# mimosa_host_fsr_sch.net
KiCad netlist of a schematic drawn in Altium Designer
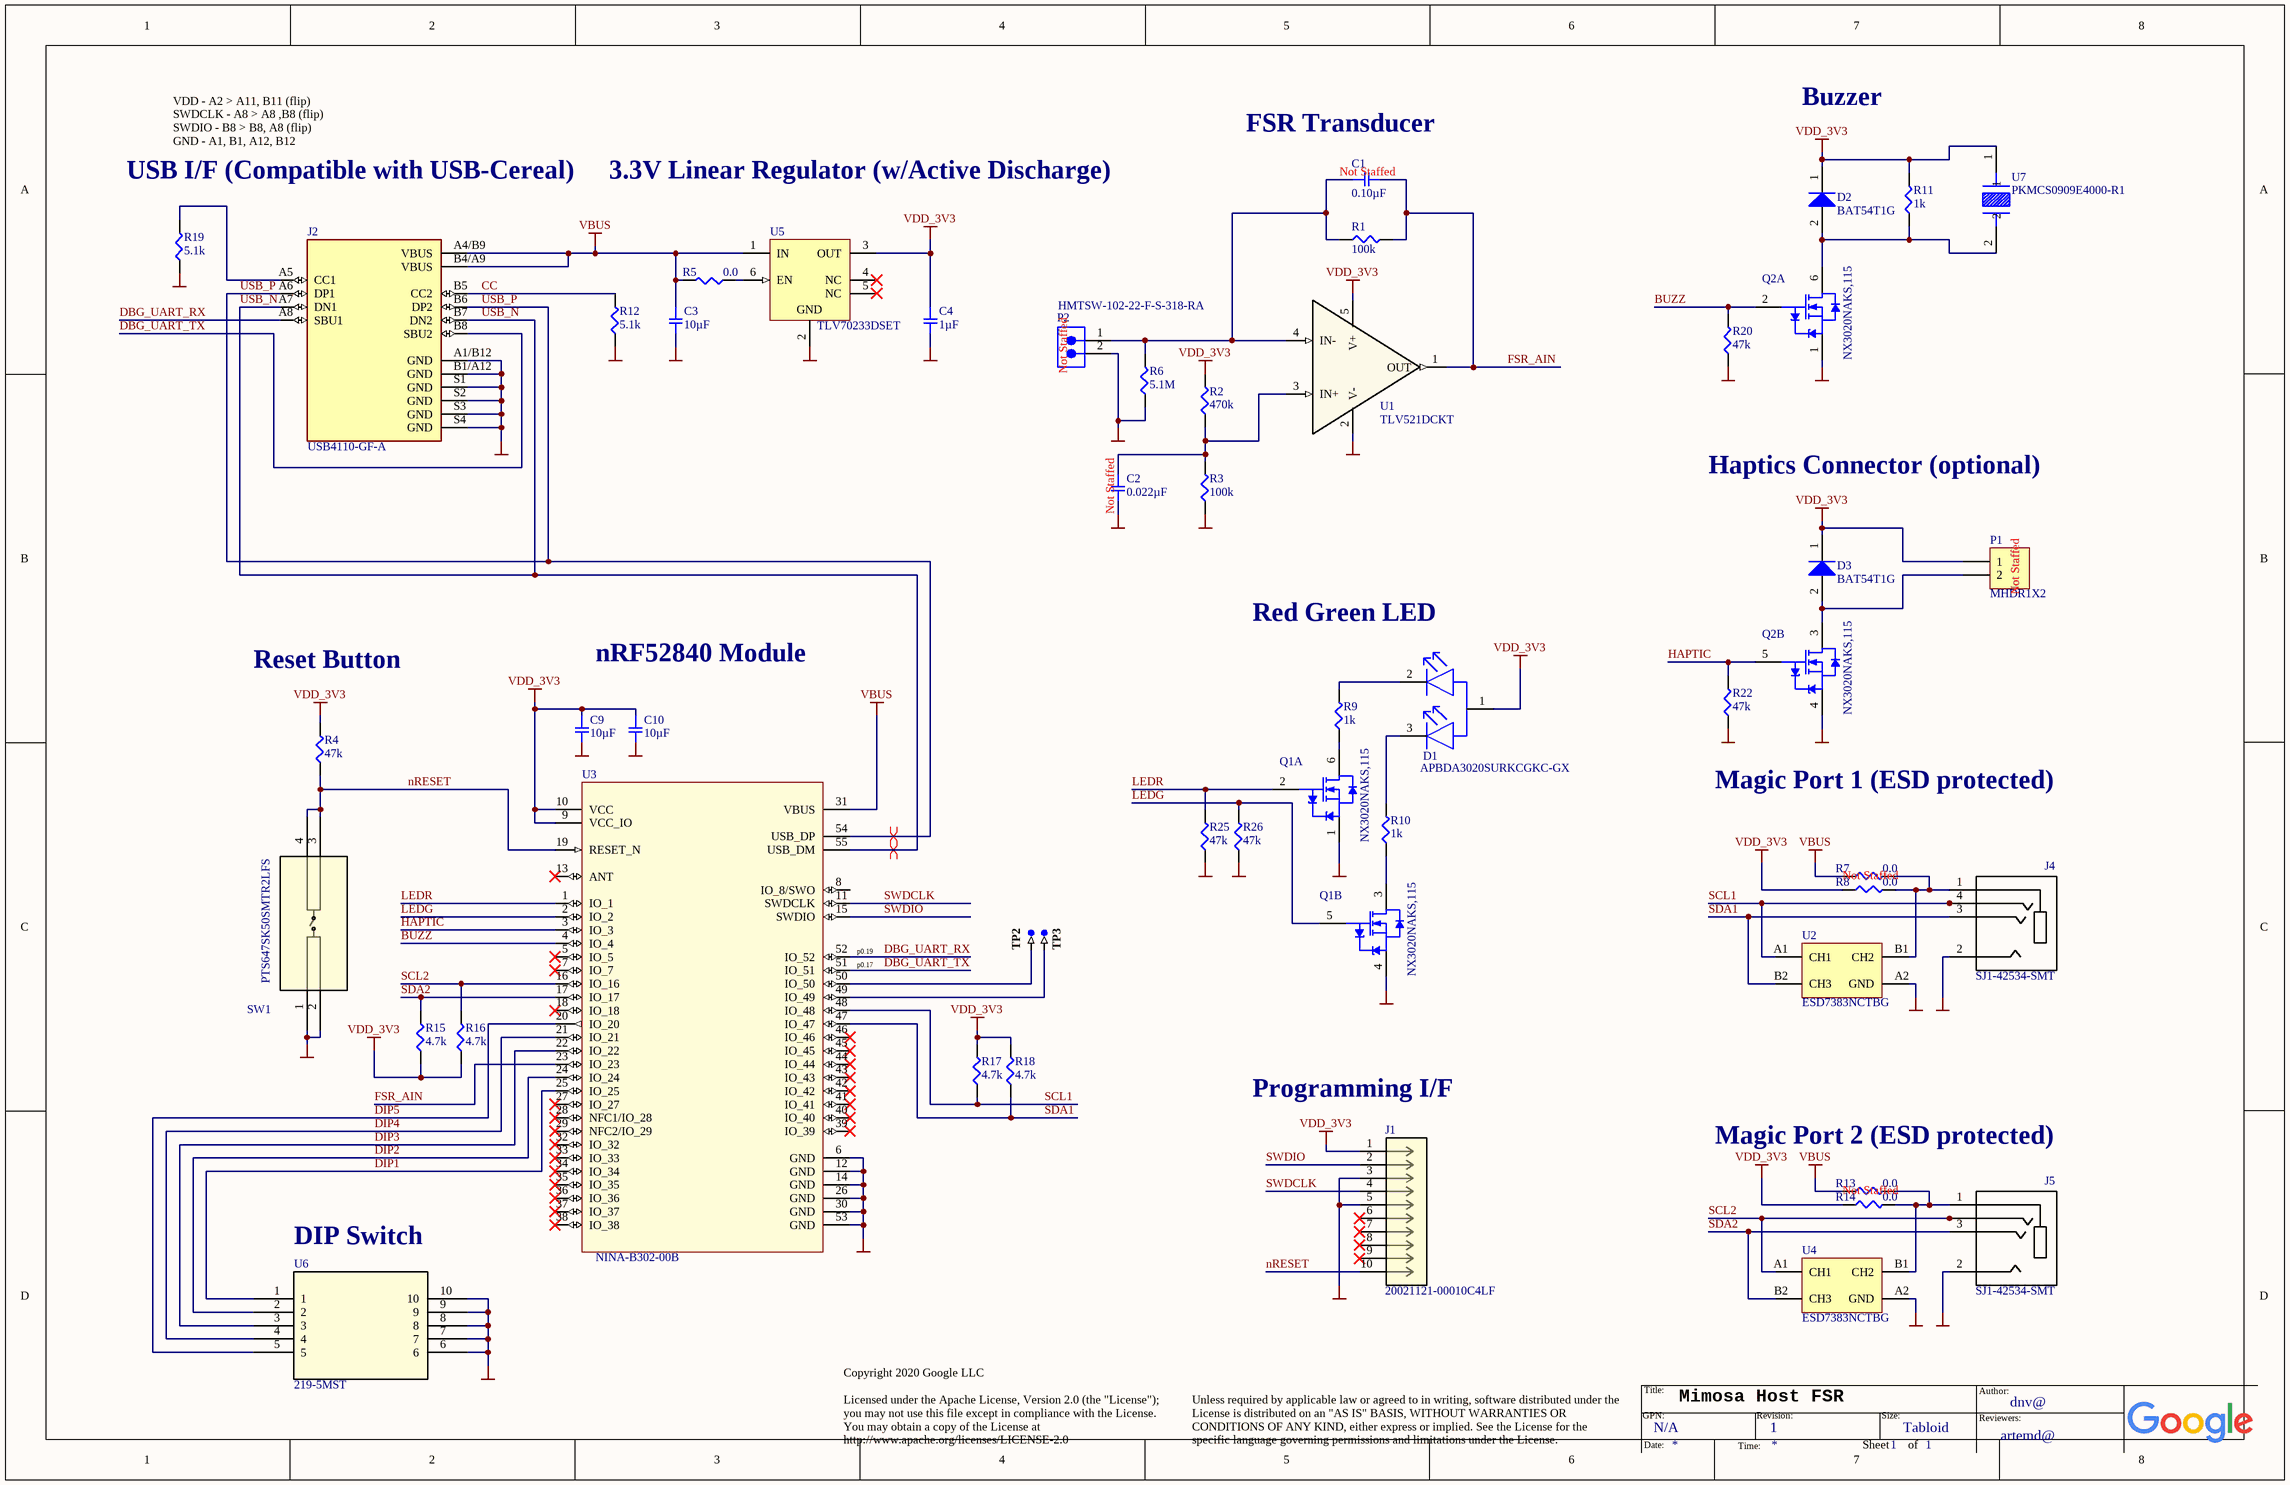
[diagram p0: mimosa_host_fsr_sch.SchDoc]

(export (version "E")
  (design (tool "Eeschema 10.0.6"))
  (components
    (comp (ref "C1")
      (value "0.10µF")
      (footprint "SMD-0201C")
      (description "CAP CER 0.1UF 10V X6S 0201")
      (fields
        (field (name "DIGI-KEY PART NUMBER") "490-12232-1-ND")
        (field (name "PART NUMBER") "GRT033C81A104KE01D")
      )
      (libsource (lib "cap_murata_0201") (part "GRT033C81A104KE01D"))
    )
    (comp (ref "C2")
      (value "0.022µF")
      (footprint "SMD-0201C")
      (description "CAP CER 0.022UF 6.3V X6S 0201")
      (fields
        (field (name "DIGI-KEY PART NUMBER") "490-8154-1-ND")
        (field (name "PART NUMBER") "GRM033C80J223KE01D")
      )
      (libsource (lib "cap_murata_0201") (part "GRM033C80J223KE01D"))
    )
    (comp (ref "C3")
      (value "10µF")
      (footprint "SMD-0402C")
      (description "CAP CER 10UF 6.3V X5R 0402")
      (fields
        (field (name "DIGI-KEY PART NUMBER") "490-13211-1-ND")
        (field (name "MPN") "GRJ155R60J106ME11D")
      )
      (libsource (lib "cap_murata_0402") (part "GRJ155R60J106ME11D"))
    )
    (comp (ref "C4")
      (value "1µF")
      (footprint "SMD-0201C")
      (description "CAP CER 1UF 6.3V X5R 0201")
      (fields
        (field (name "DIGI-KEY PART NUMBER") "490-7229-1-ND")
        (field (name "PART NUMBER") "GRM033R60J105MEA2D")
      )
      (libsource (lib "cap_murata_0201") (part "GRM033R60J105MEA2D"))
    )
    (comp (ref "C9")
      (value "10µF")
      (footprint "SMD-0402C")
      (description "CAP CER 10UF 6.3V X5R 0402")
      (fields
        (field (name "DIGI-KEY PART NUMBER") "490-13211-1-ND")
        (field (name "PART NUMBER") "GRJ155R60J106ME11D")
      )
      (libsource (lib "cap_murata_0402") (part "GRJ155R60J106ME11D"))
    )
    (comp (ref "C10")
      (value "10µF")
      (footprint "SMD-0402C")
      (description "CAP CER 10UF 6.3V X5R 0402")
      (fields
        (field (name "DIGI-KEY PART NUMBER") "490-13211-1-ND")
        (field (name "PART NUMBER") "GRJ155R60J106ME11D")
      )
      (libsource (lib "cap_murata_0402") (part "GRJ155R60J106ME11D"))
    )
    (comp (ref "D1")
      (value "APBDA3020SURKCGKC-GX")
      (footprint "Diode_Kingbright_APBDA3020SURKCGKC-GX_eec_MFG:Kingbright_0_MFG")
      (libsource (lib "Diode_Kingbright_APBDA3020SURKCGKC-GX_eec") (part "APBDA3020SURKCGKC-GX"))
    )
    (comp (ref "D2")
      (value "BAT54T1G")
      (footprint "ONSC-SOD-123-2-425-04_V")
      (description "Schottky Barrier Diode, 2-Pin SOD-123, Pb-Free, Tape and Reel")
      (fields (field (name "MANUFACTURER") "On Semiconductor"))
      (libsource (lib "diode_schottky_ON_Semi") (part "BAT54T1G"))
    )
    (comp (ref "D3")
      (value "BAT54T1G")
      (footprint "ONSC-SOD-123-2-425-04_V")
      (description "Schottky Barrier Diode, 2-Pin SOD-123, Pb-Free, Tape and Reel")
      (fields (field (name "MANUFACTURER") "On Semiconductor"))
      (libsource (lib "diode_schottky_ON_Semi") (part "BAT54T1G"))
    )
    (comp (ref "J1")
      (value "20021121-00010C4LF")
      (footprint "2020-07-28_02-37-58:CONN_00010C4LF_A")
      (description "No Description Available")
      (fields (field (name "COPYRIGHT") "Copyright (C) 2018 Accelerated Designs. All rights reserved"))
      (libsource (lib "2020-07-28_02-37-58") (part "20021121-00010C4"))
    )
    (comp (ref "J2")
      (value "USB4110-GF-A")
      (footprint "GCT_USB4110-GF-A")
      (fields (field (name "MF") "GCT") (field (name "DIGI-KEY_PART_NUMBER") "2073-USB4110-GF-A-1-ND"))
      (libsource (lib "USB4110-GF-A") (part "USB4110-GF-A"))
    )
    (comp (ref "J4")
      (value "SJ1-42534-SMT")
      (footprint "SJ1-42534-SMT:*CUI_SJ1-42534-SMT_SJ1-42534-SMT(Primary)")
      (description "2.5 mm, 4 Conductors, Right Angle, Surface Mount _SMT_, Audio Jack Connector")
      (fields
        (field (name "DIGI-KEY_PART_NUMBER") "CP1-42534SJCT-ND")
        (field (name "MANUFACTURER") "CUI Devices")
      )
      (libsource (lib "SJ1-42534-SMT") (part "SJ1-42534-SMT"))
    )
    (comp (ref "J5")
      (value "SJ1-42534-SMT")
      (footprint "SJ1-42534-SMT:*CUI_SJ1-42534-SMT_SJ1-42534-SMT(Primary)")
      (description "2.5 mm, 4 Conductors, Right Angle, Surface Mount _SMT_, Audio Jack Connector")
      (fields
        (field (name "DIGI-KEY_PART_NUMBER") "CP1-42534SJCT-ND")
        (field (name "MANUFACTURER") "CUI Devices")
      )
      (libsource (lib "SJ1-42534-SMT") (part "SJ1-42534-SMT"))
    )
    (comp (ref "P1")
      (value "MHDR1X2")
      (footprint "MHDR1X2")
      (description "Header, 2-Pin")
      (fields (field (name "PUBLISHER") "Altium Limited"))
      (libsource (lib "Miscellaneous Connectors") (part "MHDR1X2"))
    )
    (comp (ref "P2")
      (value "HMTSW-102-22-F-S-318-RA")
      (footprint "SMTC-HMTSW-102-22-X-S-318-RA")
      (fields (field (name "MANUFACTURER") "Samtec"))
      (libsource (lib "connector_samtec_2_54_mm") (part "HMTSW-102-22-F-S-318-RA"))
    )
    (comp (ref "Q1")
      (value "NX3020NAKS,115")
      (footprint "NXP-SOT363_N")
      (description "Dual N-Channel Trench MOSFET, 30 V, 0.18 A, -55 to 150 degC, 6-Pin SOT363, Tape and Reel")
      (fields (field (name "MANUFACTURER") "NXP Semiconductors"))
      (libsource (lib "transistor_NXP_standard_MOSFETs") (part "NX3020NAKS,115"))
    )
    (comp (ref "Q2")
      (value "NX3020NAKS,115")
      (footprint "NXP-SOT363_N")
      (description "Dual N-Channel Trench MOSFET, 30 V, 0.18 A, -55 to 150 degC, 6-Pin SOT363, Tape and Reel")
      (fields (field (name "MANUFACTURER") "NXP Semiconductors"))
      (libsource (lib "transistor_NXP_standard_MOSFETs") (part "NX3020NAKS,115"))
    )
    (comp (ref "R1")
      (value "100k")
      (footprint "SMD-0201-RES")
      (description "RES SMD 100K OHM 1% 1/20W 0201")
      (fields
        (field (name "PART NUMBER") "ERJ-1GEF1003C")
        (field (name "DIGI-KEY PART NUMBER") "P100KABCT-ND")
      )
      (libsource (lib "res_0201_panasonic_ERJ") (part "ERJ-1GEF1003C"))
    )
    (comp (ref "R2")
      (value "470k")
      (footprint "SMD-0201-RES")
      (description "RES SMD 470K OHM 1% 1/20W 0201")
      (fields
        (field (name "PART NUMBER") "ERJ-1GEF4703C")
        (field (name "DIGI-KEY PART NUMBER") "P470KABCT-ND")
      )
      (libsource (lib "res_0201_panasonic_ERJ") (part "ERJ-1GEF4703C"))
    )
    (comp (ref "R3")
      (value "100k")
      (footprint "SMD-0201-RES")
      (description "RES SMD 100K OHM 1% 1/20W 0201")
      (fields
        (field (name "PART NUMBER") "ERJ-1GEF1003C")
        (field (name "DIGI-KEY PART NUMBER") "P100KABCT-ND")
      )
      (libsource (lib "res_0201_panasonic_ERJ") (part "ERJ-1GEF1003C"))
    )
    (comp (ref "R4")
      (value "47k")
      (footprint "SMD-0201-RES")
      (description "RES SMD 47K OHM 1% 1/20W 0201")
      (fields
        (field (name "PART NUMBER") "ERJ-1GEF4702C")
        (field (name "DIGI-KEY PART NUMBER") "P47.0KABCT-ND")
      )
      (libsource (lib "res_0201_panasonic_ERJ") (part "ERJ-1GEF4702C"))
    )
    (comp (ref "R5")
      (value "0.0")
      (footprint "SMD-0201-RES")
      (description "RES SMD 0.0OHM JUMPER 1/20W 0201")
      (fields (field (name "PART NUMBER") "ERJ-1GE0R00C") (field (name "DIGI-KEY PART NUMBER") "P0.0AGCT-ND"))
      (libsource (lib "res_0201_panasonic_ERJ") (part "ERJ-1GE0R00C"))
    )
    (comp (ref "R6")
      (value "5.1M")
      (footprint "SMD-0201-RES")
      (description "RES SMD 5.1M OHM 5% 1/20W 0201")
      (fields
        (field (name "PART NUMBER") "ERJ-1GEJ515C")
        (field (name "DIGI-KEY PART NUMBER") "P5.1MAGCT-ND")
      )
      (libsource (lib "res_0201_panasonic_ERJ") (part "ERJ-1GEJ515C"))
    )
    (comp (ref "R7")
      (value "0.0")
      (footprint "SMD-0201-RES")
      (description "RES SMD 0.0OHM JUMPER 1/20W 0201")
      (fields (field (name "PART NUMBER") "ERJ-1GE0R00C") (field (name "DIGI-KEY PART NUMBER") "P0.0AGCT-ND"))
      (libsource (lib "res_0201_panasonic_ERJ") (part "ERJ-1GE0R00C"))
    )
    (comp (ref "R8")
      (value "0.0")
      (footprint "SMD-0201-RES")
      (description "RES SMD 0.0OHM JUMPER 1/20W 0201")
      (fields (field (name "PART NUMBER") "ERJ-1GE0R00C") (field (name "DIGI-KEY PART NUMBER") "P0.0AGCT-ND"))
      (libsource (lib "res_0201_panasonic_ERJ") (part "ERJ-1GE0R00C"))
    )
    (comp (ref "R9")
      (value "1k")
      (footprint "SMD-0201-RES")
      (description "RES SMD 1K OHM 1% 1/20W 0201")
      (fields
        (field (name "PART NUMBER") "ERJ-1GEF1001C")
        (field (name "DIGI-KEY PART NUMBER") "P1.00KABCT-ND")
      )
      (libsource (lib "res_0201_panasonic_ERJ") (part "ERJ-1GEF1001C"))
    )
    (comp (ref "R10")
      (value "1k")
      (footprint "SMD-0201-RES")
      (description "RES SMD 1K OHM 1% 1/20W 0201")
      (fields
        (field (name "PART NUMBER") "ERJ-1GEF1001C")
        (field (name "DIGI-KEY PART NUMBER") "P1.00KABCT-ND")
      )
      (libsource (lib "res_0201_panasonic_ERJ") (part "ERJ-1GEF1001C"))
    )
    (comp (ref "R11")
      (value "1k")
      (footprint "SMD-0201-RES")
      (description "RES SMD 1K OHM 1% 1/20W 0201")
      (fields
        (field (name "PART NUMBER") "ERJ-1GEF1001C")
        (field (name "DIGI-KEY PART NUMBER") "P1.00KABCT-ND")
      )
      (libsource (lib "res_0201_panasonic_ERJ") (part "ERJ-1GEF1001C"))
    )
    (comp (ref "R12")
      (value "5.1k")
      (footprint "SMD-0201-RES")
      (description "RES SMD 5.1K OHM 1% 1/20W 0201")
      (fields
        (field (name "PART NUMBER") "ERJ-1GEF5101C")
        (field (name "DIGI-KEY PART NUMBER") "P5.10KABCT-ND")
      )
      (libsource (lib "res_0201_panasonic_ERJ") (part "ERJ-1GEF5101C"))
    )
    (comp (ref "R13")
      (value "0.0")
      (footprint "SMD-0201-RES")
      (description "RES SMD 0.0OHM JUMPER 1/20W 0201")
      (fields (field (name "PART NUMBER") "ERJ-1GE0R00C") (field (name "DIGI-KEY PART NUMBER") "P0.0AGCT-ND"))
      (libsource (lib "res_0201_panasonic_ERJ") (part "ERJ-1GE0R00C"))
    )
    (comp (ref "R14")
      (value "0.0")
      (footprint "SMD-0201-RES")
      (description "RES SMD 0.0OHM JUMPER 1/20W 0201")
      (fields (field (name "PART NUMBER") "ERJ-1GE0R00C") (field (name "DIGI-KEY PART NUMBER") "P0.0AGCT-ND"))
      (libsource (lib "res_0201_panasonic_ERJ") (part "ERJ-1GE0R00C"))
    )
    (comp (ref "R15")
      (value "4.7k")
      (footprint "SMD-0201-RES")
      (description "RES SMD 4.7K OHM 1% 1/20W 0201")
      (fields
        (field (name "PART NUMBER") "ERJ-1GEF4701C")
        (field (name "DIGI-KEY PART NUMBER") "P4.70KABCT-ND")
      )
      (libsource (lib "res_0201_panasonic_ERJ") (part "ERJ-1GEF4701C"))
    )
    (comp (ref "R16")
      (value "4.7k")
      (footprint "SMD-0201-RES")
      (description "RES SMD 4.7K OHM 1% 1/20W 0201")
      (fields
        (field (name "PART NUMBER") "ERJ-1GEF4701C")
        (field (name "DIGI-KEY PART NUMBER") "P4.70KABCT-ND")
      )
      (libsource (lib "res_0201_panasonic_ERJ") (part "ERJ-1GEF4701C"))
    )
    (comp (ref "R17")
      (value "4.7k")
      (footprint "SMD-0201-RES")
      (description "RES SMD 4.7K OHM 1% 1/20W 0201")
      (fields
        (field (name "PART NUMBER") "ERJ-1GEF4701C")
        (field (name "DIGI-KEY PART NUMBER") "P4.70KABCT-ND")
      )
      (libsource (lib "res_0201_panasonic_ERJ") (part "ERJ-1GEF4701C"))
    )
    (comp (ref "R18")
      (value "4.7k")
      (footprint "SMD-0201-RES")
      (description "RES SMD 4.7K OHM 1% 1/20W 0201")
      (fields
        (field (name "PART NUMBER") "ERJ-1GEF4701C")
        (field (name "DIGI-KEY PART NUMBER") "P4.70KABCT-ND")
      )
      (libsource (lib "res_0201_panasonic_ERJ") (part "ERJ-1GEF4701C"))
    )
    (comp (ref "R19")
      (value "5.1k")
      (footprint "SMD-0201-RES")
      (description "RES SMD 5.1K OHM 1% 1/20W 0201")
      (fields
        (field (name "PART NUMBER") "ERJ-1GEF5101C")
        (field (name "DIGI-KEY PART NUMBER") "P5.10KABCT-ND")
      )
      (libsource (lib "res_0201_panasonic_ERJ") (part "ERJ-1GEF5101C"))
    )
    (comp (ref "R20")
      (value "47k")
      (footprint "SMD-0201-RES")
      (description "RES SMD 47K OHM 1% 1/20W 0201")
      (fields
        (field (name "PART NUMBER") "ERJ-1GEF4702C")
        (field (name "DIGI-KEY PART NUMBER") "P47.0KABCT-ND")
      )
      (libsource (lib "res_0201_panasonic_ERJ") (part "ERJ-1GEF4702C"))
    )
    (comp (ref "R22")
      (value "47k")
      (footprint "SMD-0201-RES")
      (description "RES SMD 47K OHM 1% 1/20W 0201")
      (fields
        (field (name "PART NUMBER") "ERJ-1GEF4702C")
        (field (name "DIGI-KEY PART NUMBER") "P47.0KABCT-ND")
      )
      (libsource (lib "res_0201_panasonic_ERJ") (part "ERJ-1GEF4702C"))
    )
    (comp (ref "R25")
      (value "47k")
      (footprint "SMD-0201-RES")
      (description "RES SMD 47K OHM 1% 1/20W 0201")
      (fields
        (field (name "PART NUMBER") "ERJ-1GEF4702C")
        (field (name "DIGI-KEY PART NUMBER") "P47.0KABCT-ND")
      )
      (libsource (lib "res_0201_panasonic_ERJ") (part "ERJ-1GEF4702C"))
    )
    (comp (ref "R26")
      (value "47k")
      (footprint "SMD-0201-RES")
      (description "RES SMD 47K OHM 1% 1/20W 0201")
      (fields
        (field (name "PART NUMBER") "ERJ-1GEF4702C")
        (field (name "DIGI-KEY PART NUMBER") "P47.0KABCT-ND")
      )
      (libsource (lib "res_0201_panasonic_ERJ") (part "ERJ-1GEF4702C"))
    )
    (comp (ref "SW1")
      (value "PTS647SK50SMTR2LFS")
      (footprint "2020-07-28_01-14-05:PTS647SK50SMTR2L")
      (description "No Description Available")
      (fields (field (name "COPYRIGHT") "Copyright (C) 2018 Accelerated Designs. All rights reserved"))
      (libsource (lib "2020-07-28_01-14-05") (part "PTS647SK50SMTR2L"))
    )
    (comp (ref "TP2")
      (value "TP-SM-C-100")
      (footprint "TP-SM-C-100")
      (description "Test Point, Surface Mount, Circular, Pad Diameter 1 mm")
      (fields (field (name "MANUFACTURER") "No Vendor"))
      (libsource (lib "Altium Content Vault") (part "TP-SM"))
    )
    (comp (ref "TP3")
      (value "TP-SM-C-100")
      (footprint "TP-SM-C-100")
      (description "Test Point, Surface Mount, Circular, Pad Diameter 1 mm")
      (fields (field (name "MANUFACTURER") "No Vendor"))
      (libsource (lib "Altium Content Vault") (part "TP-SM"))
    )
    (comp (ref "U1")
      (value "TLV521DCKT")
      (footprint "*SOT65P210X110-5N")
      (libsource (lib "TLV521DCKT") (part "TLV521DCKT"))
    )
    (comp (ref "U2")
      (value "ESD7383NCTBG")
      (footprint "ONSC-WLCSP-4-567CB-01")
      (description "USB-OTG 3-Line Protection, 4-Pin WLCSP, Pb-Free, Tape and Reel")
      (fields (field (name "MANUFACTURER") "On Semiconductor"))
      (libsource (lib "diode_esd_ON_Semi") (part "ESD7383NCTBG"))
    )
    (comp (ref "U3")
      (value "NINA-B302-00B")
      (footprint "NINA-B302-00B:NINA-B302-00B")
      (description "Bluetooth Bluetooth v5.0 Transceiver Module 2.4GHz Antenna Not Included Surface Mount")
      (fields (field (name "MANUFACTURER") "U-Blox America Inc."))
      (libsource (lib "NINA-B311-00B") (part "NINA-B311-00B"))
    )
    (comp (ref "U4")
      (value "ESD7383NCTBG")
      (footprint "ONSC-WLCSP-4-567CB-01")
      (description "USB-OTG 3-Line Protection, 4-Pin WLCSP, Pb-Free, Tape and Reel")
      (fields (field (name "MANUFACTURER") "On Semiconductor"))
      (libsource (lib "diode_esd_ON_Semi") (part "ESD7383NCTBG"))
    )
    (comp (ref "U5")
      (value "TLV70233DSET")
      (footprint "TI-DSE6_V")
      (fields (field (name "MANUFACTURER") "Texas Instruments"))
      (libsource (lib "ic_pwr_ldo_TI_single_channel_ldo_0-350mA") (part "TLV70233DSET"))
    )
    (comp (ref "U6")
      (value "219-5MST")
      (footprint "2020-07-28_03-28-19:SW5_219SMT")
      (description "No Description Available")
      (fields (field (name "COPYRIGHT") "Copyright (C) 2016 Accelerated Designs. All rights reserved"))
      (libsource (lib "2020-07-28_03-28-19") (part "219-5MST"))
    )
    (comp (ref "U7")
      (value "PKMCS0909E4000-R1")
      (footprint "XDCR_PKMCS0909E4000-R1")
      (description "Buzzers Transducer, Externally Driven Piezo 1.5V 4kHz 65dB @ 1.5V, 10cm Surface Mount Solder Pads")
      (fields (field (name "MF") "Murata") (field (name "DIGI-KEY_PART_NUMBER") "490-9647-1-ND"))
      (libsource (lib "PKMCS0909E4000-R1") (part "PKMCS0909E4000-R1"))
    )
  )
  (nets
    (net (code "1") (name "/BUZZ") (class "Default")
      (node (ref "Q2") (pin "2") (pinfunction "G1_2") (pintype "passive"))
      (node (ref "R20") (pin "2") (pinfunction "2_2") (pintype "passive"))
      (node (ref "U3") (pin "4") (pinfunction "IO_4_4") (pintype "bidirectional"))
    )
    (net (code "2") (name "/CC") (class "Default")
      (node (ref "J2") (pin "B5") (pinfunction "CC2_B5") (pintype "bidirectional"))
      (node (ref "R12") (pin "2") (pinfunction "2_2") (pintype "passive"))
    )
    (net (code "3") (name "/DBG_UART_RX") (class "Default")
      (node (ref "J2") (pin "A8") (pinfunction "SBU1_A8") (pintype "bidirectional"))
      (node (ref "U3") (pin "52") (pinfunction "IO_52_52") (pintype "bidirectional"))
    )
    (net (code "4") (name "/DBG_UART_TX") (class "Default")
      (node (ref "J2") (pin "B8") (pinfunction "SBU2_B8") (pintype "bidirectional"))
      (node (ref "U3") (pin "51") (pinfunction "IO_51_51") (pintype "bidirectional"))
    )
    (net (code "5") (name "/DIP1") (class "Default")
      (node (ref "U3") (pin "25") (pinfunction "IO_25_25") (pintype "bidirectional"))
      (node (ref "U6") (pin "1") (pinfunction "1_1") (pintype "passive"))
    )
    (net (code "6") (name "/DIP2") (class "Default")
      (node (ref "U3") (pin "24") (pinfunction "IO_24_24") (pintype "bidirectional"))
      (node (ref "U6") (pin "2") (pinfunction "2_2") (pintype "passive"))
    )
    (net (code "7") (name "/DIP3") (class "Default")
      (node (ref "U3") (pin "22") (pinfunction "IO_22_22") (pintype "bidirectional"))
      (node (ref "U6") (pin "3") (pinfunction "3_3") (pintype "passive"))
    )
    (net (code "8") (name "/DIP4") (class "Default")
      (node (ref "U3") (pin "21") (pinfunction "IO_21_21") (pintype "bidirectional"))
      (node (ref "U6") (pin "4") (pinfunction "4_4") (pintype "passive"))
    )
    (net (code "9") (name "/DIP5") (class "Default")
      (node (ref "U3") (pin "20") (pinfunction "IO_20_20") (pintype "output"))
      (node (ref "U6") (pin "5") (pinfunction "5_5") (pintype "passive"))
    )
    (net (code "10") (name "/FSR_AIN") (class "Default")
      (node (ref "C1") (pin "2") (pinfunction "2_2") (pintype "passive"))
      (node (ref "R1") (pin "2") (pinfunction "2_2") (pintype "passive"))
      (node (ref "U1") (pin "1") (pinfunction "OUT_1") (pintype "output"))
      (node (ref "U3") (pin "23") (pinfunction "IO_23_23") (pintype "bidirectional"))
    )
    (net (code "11") (name "/HAPTIC") (class "Default")
      (node (ref "Q2") (pin "5") (pinfunction "G2_5") (pintype "passive"))
      (node (ref "R22") (pin "2") (pinfunction "2_2") (pintype "passive"))
      (node (ref "U3") (pin "3") (pinfunction "IO_3_3") (pintype "bidirectional"))
    )
    (net (code "12") (name "/LEDG") (class "Default")
      (node (ref "Q1") (pin "5") (pinfunction "G2_5") (pintype "passive"))
      (node (ref "R26") (pin "2") (pinfunction "2_2") (pintype "passive"))
      (node (ref "U3") (pin "2") (pinfunction "IO_2_2") (pintype "bidirectional"))
    )
    (net (code "13") (name "/LEDR") (class "Default")
      (node (ref "Q1") (pin "2") (pinfunction "G1_2") (pintype "passive"))
      (node (ref "R25") (pin "2") (pinfunction "2_2") (pintype "passive"))
      (node (ref "U3") (pin "1") (pinfunction "IO_1_1") (pintype "bidirectional"))
    )
    (net (code "14") (name "/SCL1") (class "Default")
      (node (ref "J4") (pin "4") (pinfunction "4_4") (pintype "passive"))
      (node (ref "J4") (pin "4.1") (pinfunction "4_4.1") (pintype "passive"))
      (node (ref "R17") (pin "1") (pinfunction "1_1") (pintype "passive"))
      (node (ref "U2") (pin "A1") (pinfunction "CH1_A1") (pintype "passive"))
      (node (ref "U3") (pin "48") (pinfunction "IO_48_48") (pintype "bidirectional"))
    )
    (net (code "15") (name "/SCL2") (class "Default")
      (node (ref "J5") (pin "4") (pinfunction "4_4") (pintype "passive"))
      (node (ref "J5") (pin "4.1") (pinfunction "4_4.1") (pintype "passive"))
      (node (ref "R16") (pin "2") (pinfunction "2_2") (pintype "passive"))
      (node (ref "U3") (pin "16") (pinfunction "IO_16_16") (pintype "bidirectional"))
      (node (ref "U4") (pin "A1") (pinfunction "CH1_A1") (pintype "passive"))
    )
    (net (code "16") (name "/SDA1") (class "Default")
      (node (ref "J4") (pin "3") (pinfunction "3_3") (pintype "passive"))
      (node (ref "R18") (pin "1") (pinfunction "1_1") (pintype "passive"))
      (node (ref "U2") (pin "B2") (pinfunction "CH3_B2") (pintype "passive"))
      (node (ref "U3") (pin "47") (pinfunction "IO_47_47") (pintype "bidirectional"))
    )
    (net (code "17") (name "/SDA2") (class "Default")
      (node (ref "J5") (pin "3") (pinfunction "3_3") (pintype "passive"))
      (node (ref "R15") (pin "2") (pinfunction "2_2") (pintype "passive"))
      (node (ref "U3") (pin "17") (pinfunction "IO_17_17") (pintype "bidirectional"))
      (node (ref "U4") (pin "B2") (pinfunction "CH3_B2") (pintype "passive"))
    )
    (net (code "18") (name "/SWDCLK") (class "Default")
      (node (ref "J1") (pin "4") (pinfunction "4_4") (pintype "passive"))
      (node (ref "U3") (pin "11") (pinfunction "SWDCLK_11") (pintype "bidirectional"))
    )
    (net (code "19") (name "/SWDIO") (class "Default")
      (node (ref "J1") (pin "2") (pinfunction "2_2") (pintype "passive"))
      (node (ref "U3") (pin "15") (pinfunction "SWDIO_15") (pintype "bidirectional"))
    )
    (net (code "20") (name "/USB_N") (class "Default")
      (node (ref "J2") (pin "A7") (pinfunction "DN1_A7") (pintype "bidirectional"))
      (node (ref "J2") (pin "B7") (pinfunction "DN2_B7") (pintype "bidirectional"))
      (node (ref "U3") (pin "55") (pinfunction "USB_DM_55") (pintype "power_in"))
    )
    (net (code "21") (name "/USB_P") (class "Default")
      (node (ref "J2") (pin "A6") (pinfunction "DP1_A6") (pintype "bidirectional"))
      (node (ref "J2") (pin "B6") (pinfunction "DP2_B6") (pintype "bidirectional"))
      (node (ref "U3") (pin "54") (pinfunction "USB_DP_54") (pintype "power_in"))
    )
    (net (code "22") (name "/nRESET") (class "Default")
      (node (ref "J1") (pin "10") (pinfunction "10_10") (pintype "passive"))
      (node (ref "R4") (pin "1") (pinfunction "1_1") (pintype "passive"))
      (node (ref "SW1") (pin "3") (pinfunction "3_3") (pintype "passive"))
      (node (ref "SW1") (pin "4") (pinfunction "4_4") (pintype "passive"))
      (node (ref "U3") (pin "19") (pinfunction "RESET_N_19") (pintype "input"))
    )
    (net (code "23") (name "GND") (class "Default")
      (node (ref "C10") (pin "2") (pinfunction "2_2") (pintype "passive"))
      (node (ref "C2") (pin "2") (pinfunction "2_2") (pintype "passive"))
      (node (ref "C3") (pin "2") (pinfunction "2_2") (pintype "passive"))
      (node (ref "C4") (pin "2") (pinfunction "2_2") (pintype "passive"))
      (node (ref "C9") (pin "2") (pinfunction "2_2") (pintype "passive"))
      (node (ref "J1") (pin "3") (pinfunction "3_3") (pintype "passive"))
      (node (ref "J1") (pin "5") (pinfunction "5_5") (pintype "passive"))
      (node (ref "J2") (pin "A1/B12") (pinfunction "GND_A1/B12") (pintype "power_in"))
      (node (ref "J2") (pin "B1/A12") (pinfunction "GND_B1/A12") (pintype "power_in"))
      (node (ref "J2") (pin "S1") (pinfunction "GND_S1") (pintype "power_in"))
      (node (ref "J2") (pin "S2") (pinfunction "GND_S2") (pintype "power_in"))
      (node (ref "J2") (pin "S3") (pinfunction "GND_S3") (pintype "power_in"))
      (node (ref "J2") (pin "S4") (pinfunction "GND_S4") (pintype "power_in"))
      (node (ref "J4") (pin "2") (pinfunction "2_2") (pintype "passive"))
      (node (ref "J5") (pin "2") (pinfunction "2_2") (pintype "passive"))
      (node (ref "P2") (pin "2") (pinfunction "2_2") (pintype "passive"))
      (node (ref "Q1") (pin "1") (pinfunction "S1_1") (pintype "passive"))
      (node (ref "Q1") (pin "4") (pinfunction "S2_4") (pintype "passive"))
      (node (ref "Q2") (pin "1") (pinfunction "S1_1") (pintype "passive"))
      (node (ref "Q2") (pin "4") (pinfunction "S2_4") (pintype "passive"))
      (node (ref "R12") (pin "1") (pinfunction "1_1") (pintype "passive"))
      (node (ref "R19") (pin "1") (pinfunction "1_1") (pintype "passive"))
      (node (ref "R20") (pin "1") (pinfunction "1_1") (pintype "passive"))
      (node (ref "R22") (pin "1") (pinfunction "1_1") (pintype "passive"))
      (node (ref "R25") (pin "1") (pinfunction "1_1") (pintype "passive"))
      (node (ref "R26") (pin "1") (pinfunction "1_1") (pintype "passive"))
      (node (ref "R3") (pin "1") (pinfunction "1_1") (pintype "passive"))
      (node (ref "R6") (pin "1") (pinfunction "1_1") (pintype "passive"))
      (node (ref "SW1") (pin "1") (pinfunction "1_1") (pintype "passive"))
      (node (ref "SW1") (pin "2") (pinfunction "2_2") (pintype "passive"))
      (node (ref "U1") (pin "2") (pinfunction "V-_2") (pintype "power_in"))
      (node (ref "U2") (pin "A2") (pinfunction "GND_A2") (pintype "power_in"))
      (node (ref "U3") (pin "12") (pinfunction "GND_12") (pintype "power_in"))
      (node (ref "U3") (pin "14") (pinfunction "GND_14") (pintype "power_in"))
      (node (ref "U3") (pin "26") (pinfunction "GND_26") (pintype "power_in"))
      (node (ref "U3") (pin "30") (pinfunction "GND_30") (pintype "power_in"))
      (node (ref "U3") (pin "53") (pinfunction "GND_53") (pintype "power_in"))
      (node (ref "U3") (pin "6") (pinfunction "GND_6") (pintype "power_in"))
      (node (ref "U4") (pin "A2") (pinfunction "GND_A2") (pintype "power_in"))
      (node (ref "U5") (pin "2") (pinfunction "GND_2") (pintype "power_in"))
      (node (ref "U6") (pin "10") (pinfunction "10_10") (pintype "passive"))
      (node (ref "U6") (pin "6") (pinfunction "6_6") (pintype "passive"))
      (node (ref "U6") (pin "7") (pinfunction "7_7") (pintype "passive"))
      (node (ref "U6") (pin "8") (pinfunction "8_8") (pintype "passive"))
      (node (ref "U6") (pin "9") (pinfunction "9_9") (pintype "passive"))
    )
    (net (code "24") (name "Net-(D1-Green_C)") (class "Default")
      (node (ref "D1") (pin "3") (pinfunction "Green_C_3") (pintype "passive"))
      (node (ref "R10") (pin "2") (pinfunction "2_2") (pintype "passive"))
    )
    (net (code "25") (name "Net-(D1-Red_C)") (class "Default")
      (node (ref "D1") (pin "2") (pinfunction "Red_C_2") (pintype "passive"))
      (node (ref "R9") (pin "2") (pinfunction "2_2") (pintype "passive"))
    )
    (net (code "26") (name "Net-(D2-A)") (class "Default")
      (node (ref "D2") (pin "2") (pinfunction "A_2") (pintype "passive"))
      (node (ref "Q2") (pin "6") (pinfunction "D1_6") (pintype "passive"))
      (node (ref "R11") (pin "1") (pinfunction "1_1") (pintype "passive"))
      (node (ref "U7") (pin "2") (pinfunction "2_2") (pintype "passive"))
    )
    (net (code "27") (name "Net-(D3-A)") (class "Default")
      (node (ref "D3") (pin "2") (pinfunction "A_2") (pintype "passive"))
      (node (ref "P1") (pin "2") (pinfunction "2_2") (pintype "passive"))
      (node (ref "Q2") (pin "3") (pinfunction "D2_3") (pintype "passive"))
    )
    (net (code "28") (name "Net-(J2-CC1)") (class "Default")
      (node (ref "J2") (pin "A5") (pinfunction "CC1_A5") (pintype "bidirectional"))
      (node (ref "R19") (pin "2") (pinfunction "2_2") (pintype "passive"))
    )
    (net (code "29") (name "Net-(Q1A-D1)") (class "Default")
      (node (ref "Q1") (pin "6") (pinfunction "D1_6") (pintype "passive"))
      (node (ref "R9") (pin "1") (pinfunction "1_1") (pintype "passive"))
    )
    (net (code "30") (name "Net-(Q1B-D2)") (class "Default")
      (node (ref "Q1") (pin "3") (pinfunction "D2_3") (pintype "passive"))
      (node (ref "R10") (pin "1") (pinfunction "1_1") (pintype "passive"))
    )
    (net (code "31") (name "Net-(U1-IN+)") (class "Default")
      (node (ref "C2") (pin "1") (pinfunction "1_1") (pintype "passive"))
      (node (ref "R2") (pin "1") (pinfunction "1_1") (pintype "passive"))
      (node (ref "R3") (pin "2") (pinfunction "2_2") (pintype "passive"))
      (node (ref "U1") (pin "3") (pinfunction "IN+_3") (pintype "input"))
    )
    (net (code "32") (name "Net-(U1-IN-)") (class "Default")
      (node (ref "C1") (pin "1") (pinfunction "1_1") (pintype "passive"))
      (node (ref "P2") (pin "1") (pinfunction "1_1") (pintype "passive"))
      (node (ref "R1") (pin "1") (pinfunction "1_1") (pintype "passive"))
      (node (ref "R6") (pin "2") (pinfunction "2_2") (pintype "passive"))
      (node (ref "U1") (pin "4") (pinfunction "IN-_4") (pintype "input"))
    )
    (net (code "33") (name "Net-(U2-CH2)") (class "Default")
      (node (ref "J4") (pin "1") (pinfunction "1_1") (pintype "passive"))
      (node (ref "R7") (pin "2") (pinfunction "2_2") (pintype "passive"))
      (node (ref "R8") (pin "2") (pinfunction "2_2") (pintype "passive"))
      (node (ref "U2") (pin "B1") (pinfunction "CH2_B1") (pintype "passive"))
    )
    (net (code "34") (name "Net-(U3-IO_49)") (class "Default")
      (node (ref "TP3") (pin "1") (pinfunction "1_1") (pintype "input"))
      (node (ref "U3") (pin "49") (pinfunction "IO_49_49") (pintype "bidirectional"))
    )
    (net (code "35") (name "Net-(U3-IO_50)") (class "Default")
      (node (ref "TP2") (pin "1") (pinfunction "1_1") (pintype "input"))
      (node (ref "U3") (pin "50") (pinfunction "IO_50_50") (pintype "bidirectional"))
    )
    (net (code "36") (name "Net-(U4-CH2)") (class "Default")
      (node (ref "J5") (pin "1") (pinfunction "1_1") (pintype "passive"))
      (node (ref "R13") (pin "2") (pinfunction "2_2") (pintype "passive"))
      (node (ref "R14") (pin "2") (pinfunction "2_2") (pintype "passive"))
      (node (ref "U4") (pin "B1") (pinfunction "CH2_B1") (pintype "passive"))
    )
    (net (code "37") (name "Net-(U5-EN)") (class "Default")
      (node (ref "R5") (pin "1") (pinfunction "1_1") (pintype "passive"))
      (node (ref "U5") (pin "6") (pinfunction "EN_6") (pintype "input"))
    )
    (net (code "38") (name "VBUS") (class "Default")
      (node (ref "C3") (pin "1") (pinfunction "1_1") (pintype "passive"))
      (node (ref "J2") (pin "A4/B9") (pinfunction "VBUS_A4/B9") (pintype "power_in"))
      (node (ref "J2") (pin "B4/A9") (pinfunction "VBUS_B4/A9") (pintype "power_in"))
      (node (ref "R13") (pin "1") (pinfunction "1_1") (pintype "passive"))
      (node (ref "R5") (pin "2") (pinfunction "2_2") (pintype "passive"))
      (node (ref "R7") (pin "1") (pinfunction "1_1") (pintype "passive"))
      (node (ref "U3") (pin "31") (pinfunction "VBUS_31") (pintype "power_in"))
      (node (ref "U5") (pin "1") (pinfunction "IN_1") (pintype "power_in"))
    )
    (net (code "39") (name "VDD_3V3") (class "Default")
      (node (ref "C10") (pin "1") (pinfunction "1_1") (pintype "passive"))
      (node (ref "C4") (pin "1") (pinfunction "1_1") (pintype "passive"))
      (node (ref "C9") (pin "1") (pinfunction "1_1") (pintype "passive"))
      (node (ref "D1") (pin "1") (pinfunction "Common_Anode_1") (pintype "passive"))
      (node (ref "D2") (pin "1") (pinfunction "K_1") (pintype "passive"))
      (node (ref "D3") (pin "1") (pinfunction "K_1") (pintype "passive"))
      (node (ref "J1") (pin "1") (pinfunction "1_1") (pintype "passive"))
      (node (ref "P1") (pin "1") (pinfunction "1_1") (pintype "passive"))
      (node (ref "R11") (pin "2") (pinfunction "2_2") (pintype "passive"))
      (node (ref "R14") (pin "1") (pinfunction "1_1") (pintype "passive"))
      (node (ref "R15") (pin "1") (pinfunction "1_1") (pintype "passive"))
      (node (ref "R16") (pin "1") (pinfunction "1_1") (pintype "passive"))
      (node (ref "R17") (pin "2") (pinfunction "2_2") (pintype "passive"))
      (node (ref "R18") (pin "2") (pinfunction "2_2") (pintype "passive"))
      (node (ref "R2") (pin "2") (pinfunction "2_2") (pintype "passive"))
      (node (ref "R4") (pin "2") (pinfunction "2_2") (pintype "passive"))
      (node (ref "R8") (pin "1") (pinfunction "1_1") (pintype "passive"))
      (node (ref "U1") (pin "5") (pinfunction "V+_5") (pintype "power_in"))
      (node (ref "U3") (pin "10") (pinfunction "VCC_10") (pintype "power_in"))
      (node (ref "U3") (pin "9") (pinfunction "VCC_IO_9") (pintype "power_in"))
      (node (ref "U5") (pin "3") (pinfunction "OUT_3") (pintype "power_in"))
      (node (ref "U7") (pin "1") (pinfunction "1_1") (pintype "passive"))
    )
    (net (code "40") (name "unconnected-(J1-Pad6)") (class "Default")
      (node (ref "J1") (pin "6") (pinfunction "6_6") (pintype "passive+no_connect"))
    )
    (net (code "41") (name "unconnected-(J1-Pad7)") (class "Default")
      (node (ref "J1") (pin "7") (pinfunction "7_7") (pintype "passive+no_connect"))
    )
    (net (code "42") (name "unconnected-(J1-Pad8)") (class "Default")
      (node (ref "J1") (pin "8") (pinfunction "8_8") (pintype "passive+no_connect"))
    )
    (net (code "43") (name "unconnected-(J1-Pad9)") (class "Default")
      (node (ref "J1") (pin "9") (pinfunction "9_9") (pintype "passive+no_connect"))
    )
    (net (code "44") (name "unconnected-(U3-ANT-Pad13)") (class "Default")
      (node (ref "U3") (pin "13") (pinfunction "ANT_13") (pintype "bidirectional+no_connect"))
    )
    (net (code "45") (name "unconnected-(U3-IO_5-Pad5)") (class "Default")
      (node (ref "U3") (pin "5") (pinfunction "IO_5_5") (pintype "bidirectional+no_connect"))
    )
    (net (code "46") (name "unconnected-(U3-IO_7-Pad7)") (class "Default")
      (node (ref "U3") (pin "7") (pinfunction "IO_7_7") (pintype "bidirectional+no_connect"))
    )
    (net (code "47") (name "unconnected-(U3-IO_8{slash}SWO-Pad8)") (class "Default")
      (node (ref "U3") (pin "8") (pinfunction "IO_8/SWO_8") (pintype "bidirectional"))
    )
    (net (code "48") (name "unconnected-(U3-IO_18-Pad18)") (class "Default")
      (node (ref "U3") (pin "18") (pinfunction "IO_18_18") (pintype "bidirectional+no_connect"))
    )
    (net (code "49") (name "unconnected-(U3-IO_27-Pad27)") (class "Default")
      (node (ref "U3") (pin "27") (pinfunction "IO_27_27") (pintype "bidirectional+no_connect"))
    )
    (net (code "50") (name "unconnected-(U3-IO_32-Pad32)") (class "Default")
      (node (ref "U3") (pin "32") (pinfunction "IO_32_32") (pintype "bidirectional+no_connect"))
    )
    (net (code "51") (name "unconnected-(U3-IO_33-Pad33)") (class "Default")
      (node (ref "U3") (pin "33") (pinfunction "IO_33_33") (pintype "bidirectional+no_connect"))
    )
    (net (code "52") (name "unconnected-(U3-IO_34-Pad34)") (class "Default")
      (node (ref "U3") (pin "34") (pinfunction "IO_34_34") (pintype "bidirectional+no_connect"))
    )
    (net (code "53") (name "unconnected-(U3-IO_35-Pad35)") (class "Default")
      (node (ref "U3") (pin "35") (pinfunction "IO_35_35") (pintype "bidirectional+no_connect"))
    )
    (net (code "54") (name "unconnected-(U3-IO_36-Pad36)") (class "Default")
      (node (ref "U3") (pin "36") (pinfunction "IO_36_36") (pintype "bidirectional+no_connect"))
    )
    (net (code "55") (name "unconnected-(U3-IO_37-Pad37)") (class "Default")
      (node (ref "U3") (pin "37") (pinfunction "IO_37_37") (pintype "bidirectional+no_connect"))
    )
    (net (code "56") (name "unconnected-(U3-IO_38-Pad38)") (class "Default")
      (node (ref "U3") (pin "38") (pinfunction "IO_38_38") (pintype "bidirectional+no_connect"))
    )
    (net (code "57") (name "unconnected-(U3-IO_39-Pad39)") (class "Default")
      (node (ref "U3") (pin "39") (pinfunction "IO_39_39") (pintype "bidirectional+no_connect"))
    )
    (net (code "58") (name "unconnected-(U3-IO_40-Pad40)") (class "Default")
      (node (ref "U3") (pin "40") (pinfunction "IO_40_40") (pintype "bidirectional+no_connect"))
    )
    (net (code "59") (name "unconnected-(U3-IO_41-Pad41)") (class "Default")
      (node (ref "U3") (pin "41") (pinfunction "IO_41_41") (pintype "bidirectional+no_connect"))
    )
    (net (code "60") (name "unconnected-(U3-IO_42-Pad42)") (class "Default")
      (node (ref "U3") (pin "42") (pinfunction "IO_42_42") (pintype "bidirectional+no_connect"))
    )
    (net (code "61") (name "unconnected-(U3-IO_43-Pad43)") (class "Default")
      (node (ref "U3") (pin "43") (pinfunction "IO_43_43") (pintype "bidirectional+no_connect"))
    )
    (net (code "62") (name "unconnected-(U3-IO_44-Pad44)") (class "Default")
      (node (ref "U3") (pin "44") (pinfunction "IO_44_44") (pintype "bidirectional+no_connect"))
    )
    (net (code "63") (name "unconnected-(U3-IO_45-Pad45)") (class "Default")
      (node (ref "U3") (pin "45") (pinfunction "IO_45_45") (pintype "bidirectional+no_connect"))
    )
    (net (code "64") (name "unconnected-(U3-IO_46-Pad46)") (class "Default")
      (node (ref "U3") (pin "46") (pinfunction "IO_46_46") (pintype "bidirectional+no_connect"))
    )
    (net (code "65") (name "unconnected-(U3-NFC1{slash}IO_28-Pad28)") (class "Default")
      (node (ref "U3") (pin "28") (pinfunction "NFC1/IO_28_28") (pintype "bidirectional+no_connect"))
    )
    (net (code "66") (name "unconnected-(U3-NFC2{slash}IO_29-Pad29)") (class "Default")
      (node (ref "U3") (pin "29") (pinfunction "NFC2/IO_29_29") (pintype "bidirectional+no_connect"))
    )
    (net (code "67") (name "unconnected-(U5-NC-Pad4)") (class "Default")
      (node (ref "U5") (pin "4") (pinfunction "NC_4") (pintype "passive+no_connect"))
    )
    (net (code "68") (name "unconnected-(U5-NC-Pad5)") (class "Default")
      (node (ref "U5") (pin "5") (pinfunction "NC_5") (pintype "passive+no_connect"))
    )
  )
)
